# NS_ARM_Control_07_17_2017.net
KiCad netlist of a schematic drawn in EAGLE
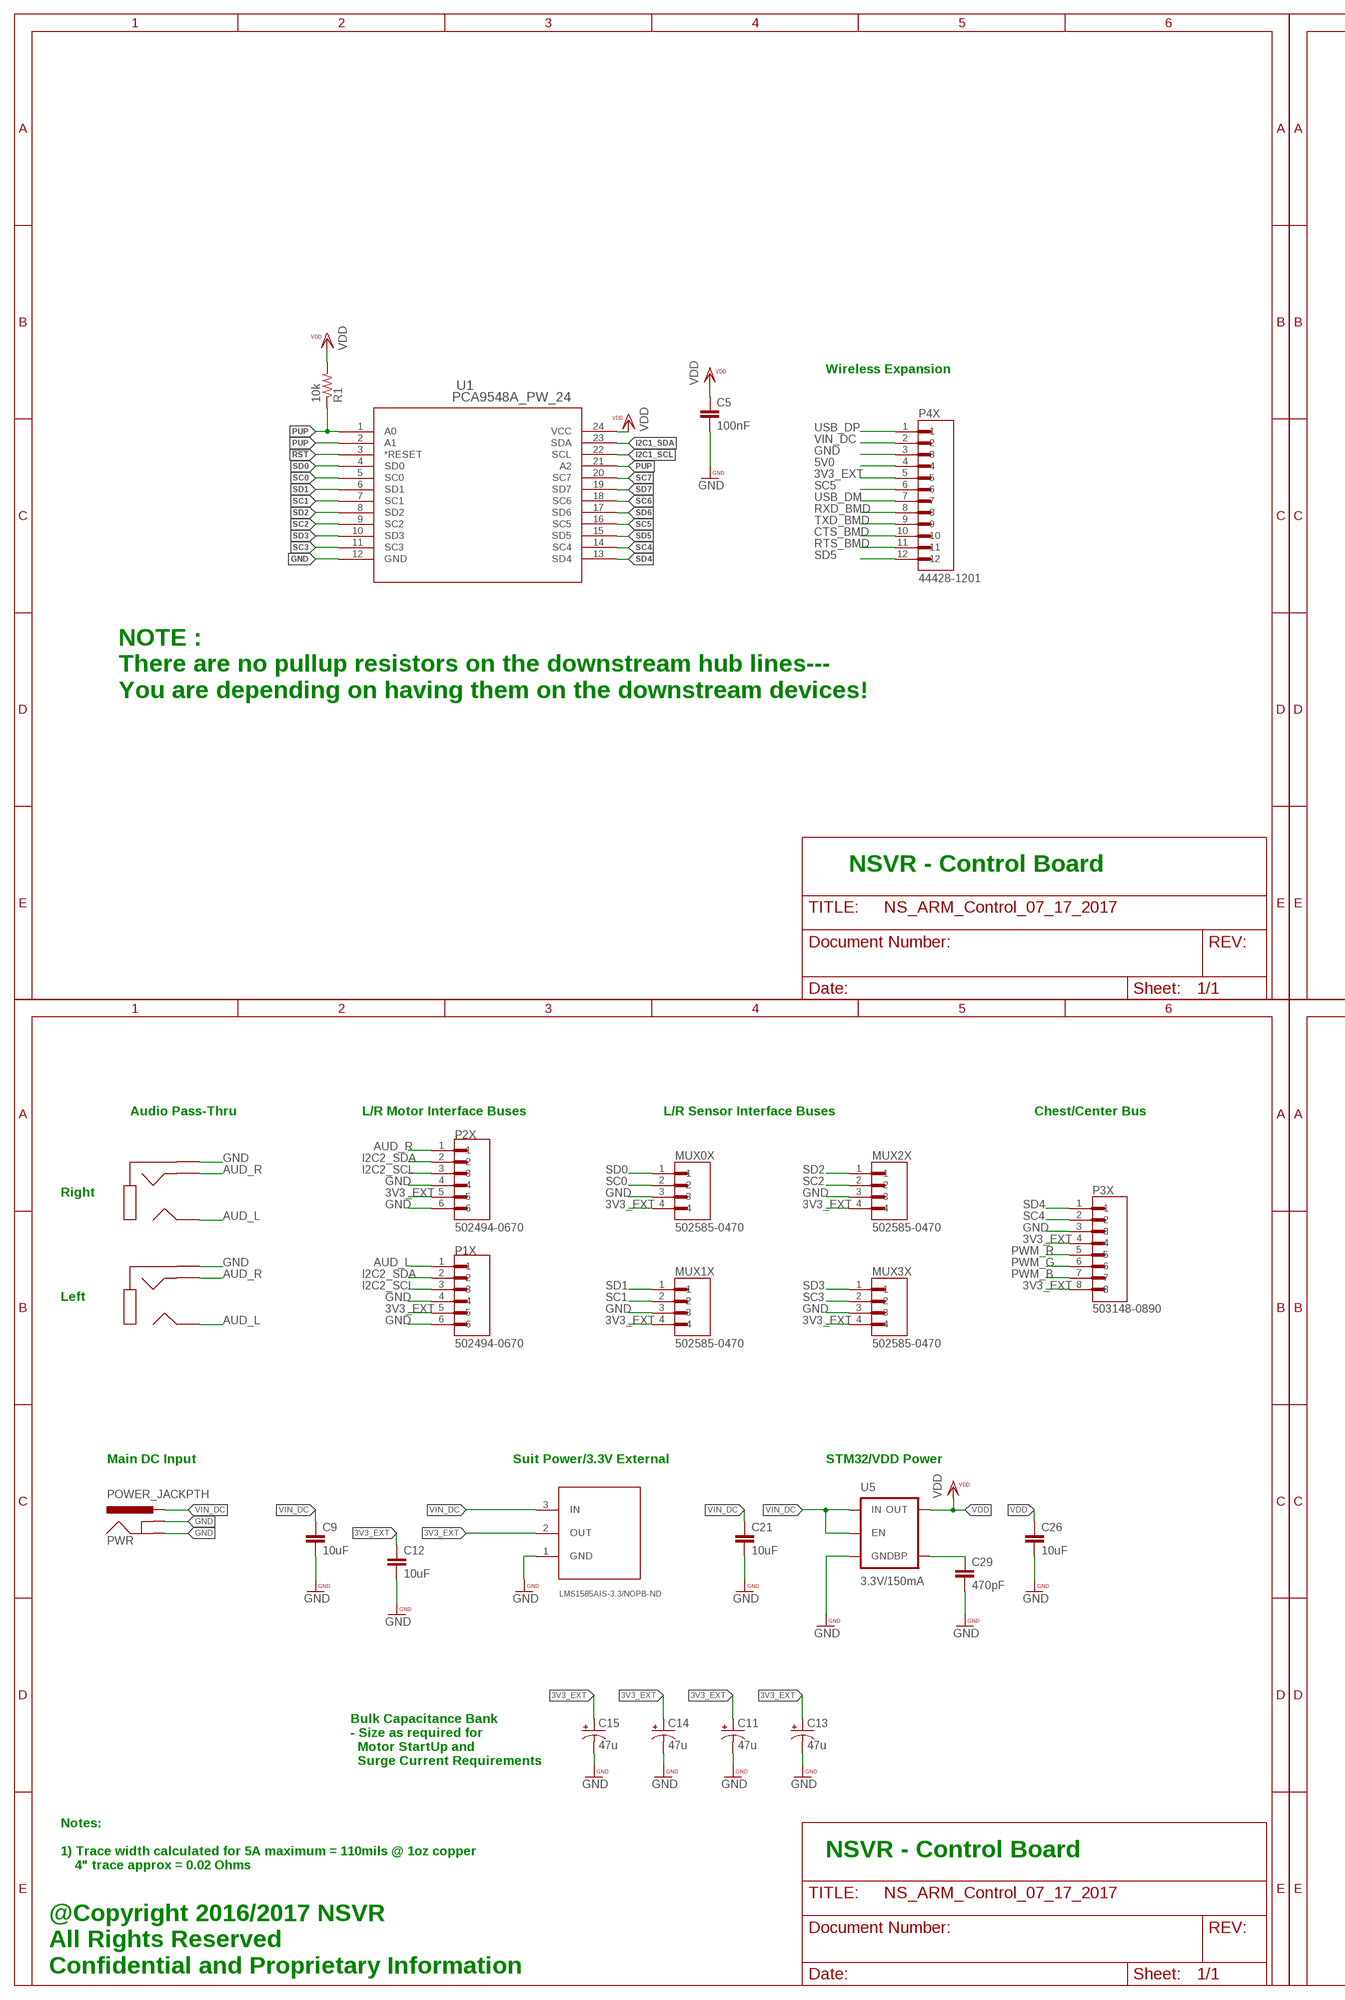
[diagram p0: schematic, sheet 1, part 1 of 2]
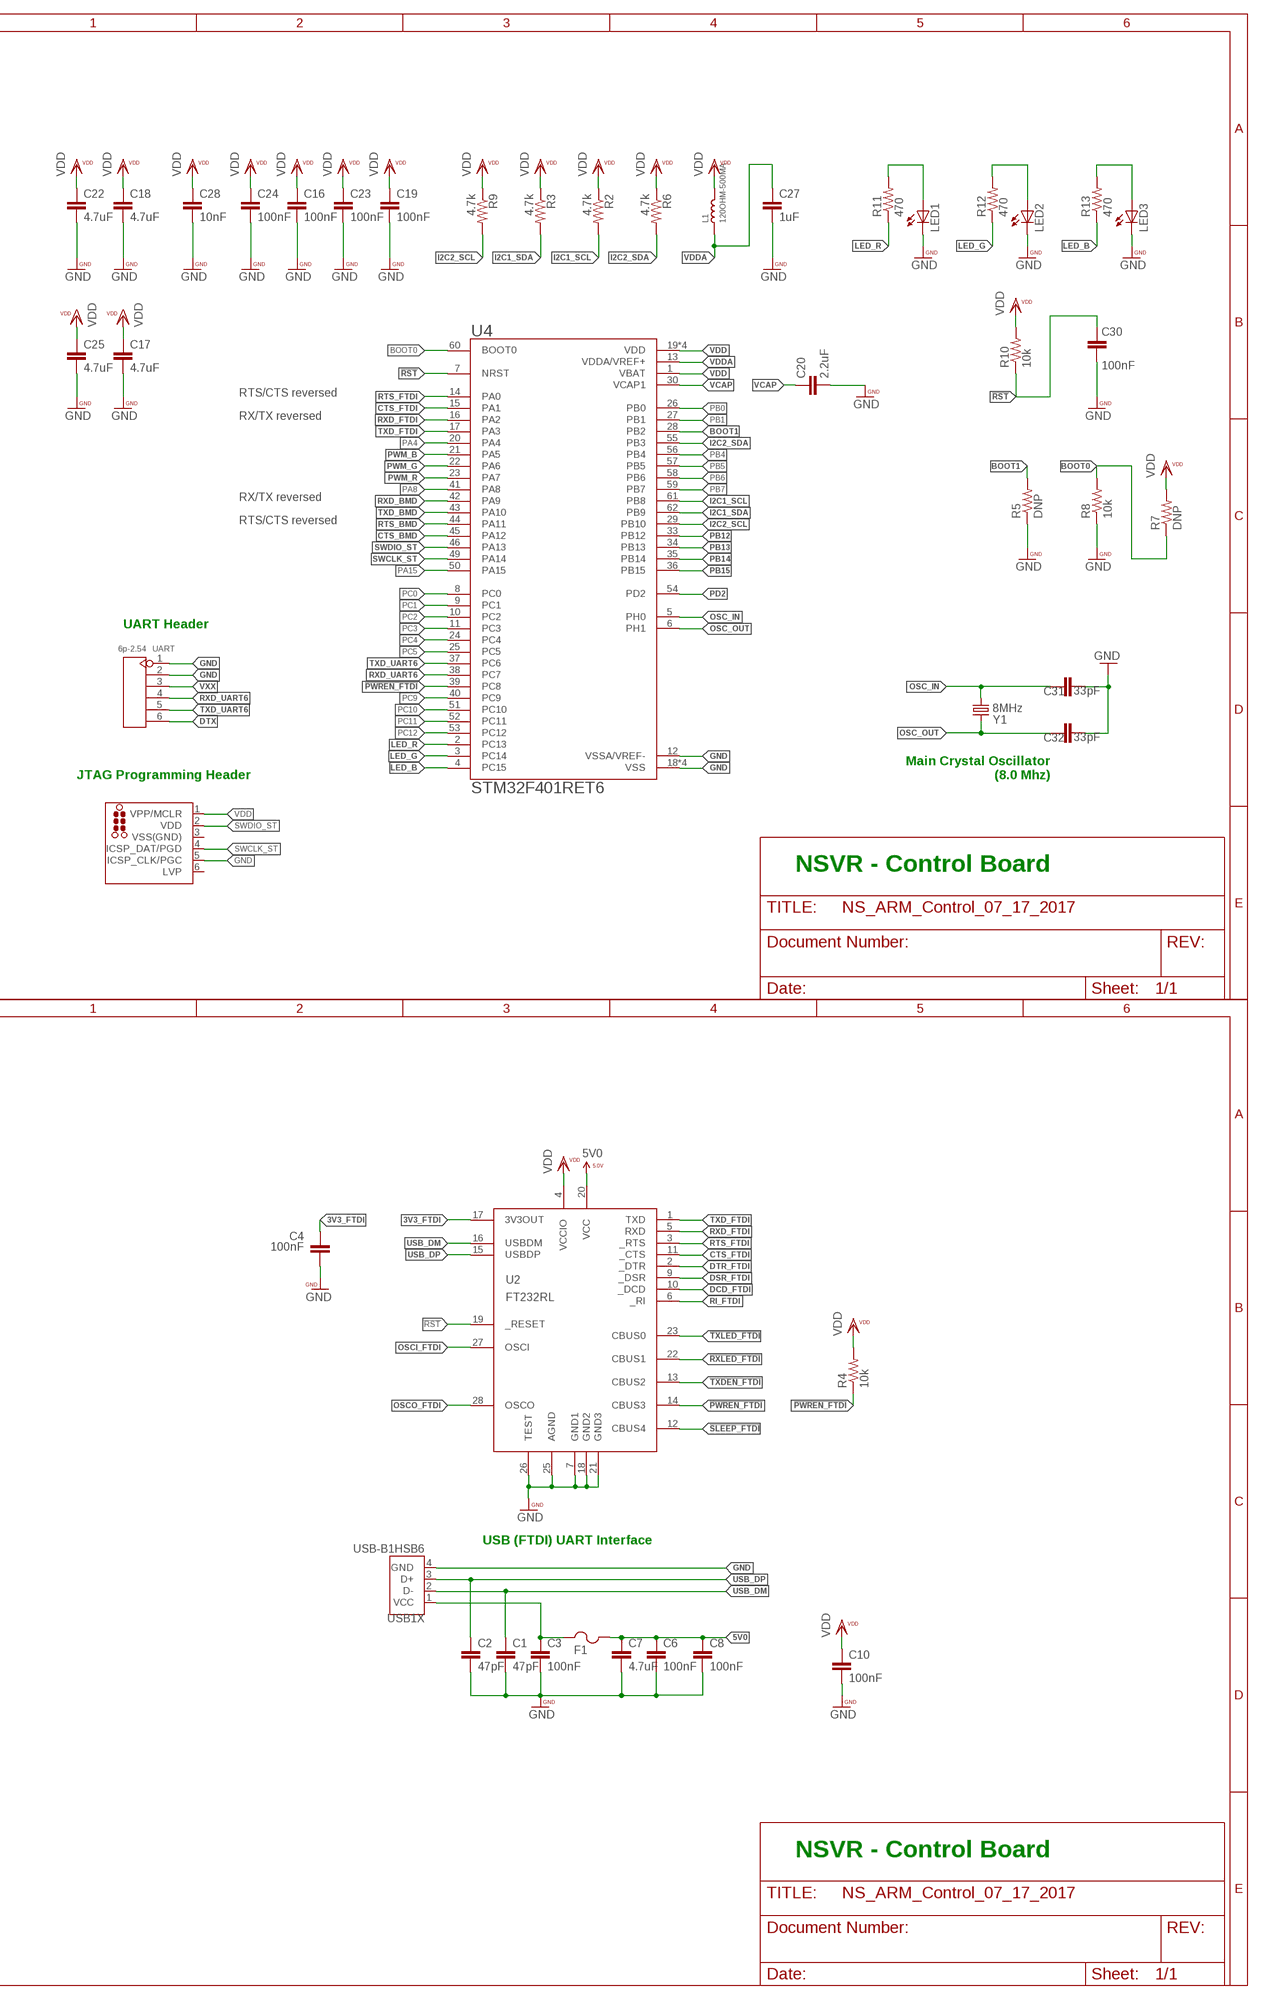
[diagram p1: schematic, sheet 1, part 2 of 2]

(export (version "E")
  (design (tool "Eeschema 10.0.6"))
  (components
    (comp (ref "C1")
      (value "47pF")
      (footprint "eagle-import:0402-CAP")
      (libsource (lib "eagle-import") (part "CAP0402-CAP"))
    )
    (comp (ref "C2")
      (value "47pF")
      (footprint "eagle-import:0402-CAP")
      (libsource (lib "eagle-import") (part "CAP0402-CAP"))
    )
    (comp (ref "C3")
      (value "100nF")
      (footprint "eagle-import:0402-CAP")
      (libsource (lib "eagle-import") (part "CAP0402-CAP"))
    )
    (comp (ref "C4")
      (value "100nF")
      (footprint "eagle-import:0402-CAP")
      (libsource (lib "eagle-import") (part "CAP0402-CAP"))
    )
    (comp (ref "C5")
      (value "100nF")
      (footprint "eagle-import:0402-CAP")
      (libsource (lib "eagle-import") (part "CAP0402-CAP"))
    )
    (comp (ref "C6")
      (value "100nF")
      (footprint "eagle-import:0402-CAP")
      (libsource (lib "eagle-import") (part "CAP0402-CAP"))
    )
    (comp (ref "C7")
      (value "4.7uF")
      (footprint "eagle-import:0402-CAP")
      (libsource (lib "eagle-import") (part "CAP0402-CAP"))
    )
    (comp (ref "C8")
      (value "100nF")
      (footprint "eagle-import:0402-CAP")
      (libsource (lib "eagle-import") (part "CAP0402-CAP"))
    )
    (comp (ref "C9")
      (value "10uF")
      (footprint "eagle-import:0603-CAP")
      (libsource (lib "eagle-import") (part "CAP0603-CAP"))
    )
    (comp (ref "C10")
      (value "100nF")
      (footprint "eagle-import:0402-CAP")
      (libsource (lib "eagle-import") (part "CAP0402-CAP"))
    )
    (comp (ref "C11")
      (value "47u")
      (footprint "eagle-import:PANASONIC_D")
      (libsource (lib "eagle-import") (part "CAP_POLD"))
    )
    (comp (ref "C12")
      (value "10uF")
      (footprint "eagle-import:0603-CAP")
      (libsource (lib "eagle-import") (part "CAP0603-CAP"))
    )
    (comp (ref "C13")
      (value "47u")
      (footprint "eagle-import:PANASONIC_D")
      (libsource (lib "eagle-import") (part "CAP_POLD"))
    )
    (comp (ref "C14")
      (value "47u")
      (footprint "eagle-import:PANASONIC_D")
      (libsource (lib "eagle-import") (part "CAP_POLD"))
    )
    (comp (ref "C15")
      (value "47u")
      (footprint "eagle-import:PANASONIC_D")
      (libsource (lib "eagle-import") (part "CAP_POLD"))
    )
    (comp (ref "C16")
      (value "100nF")
      (footprint "eagle-import:0402-CAP")
      (libsource (lib "eagle-import") (part "CAP0402-CAP"))
    )
    (comp (ref "C17")
      (value "4.7uF")
      (footprint "eagle-import:0402-CAP")
      (libsource (lib "eagle-import") (part "CAP0402-CAP"))
    )
    (comp (ref "C18")
      (value "4.7uF")
      (footprint "eagle-import:0402-CAP")
      (libsource (lib "eagle-import") (part "CAP0402-CAP"))
    )
    (comp (ref "C19")
      (value "100nF")
      (footprint "eagle-import:0402-CAP")
      (libsource (lib "eagle-import") (part "CAP0402-CAP"))
    )
    (comp (ref "C20")
      (value "2.2uF")
      (footprint "eagle-import:0402-CAP")
      (libsource (lib "eagle-import") (part "CAP0402-CAP"))
    )
    (comp (ref "C21")
      (value "10uF")
      (footprint "eagle-import:0603-CAP")
      (libsource (lib "eagle-import") (part "CAP0603-CAP"))
    )
    (comp (ref "C22")
      (value "4.7uF")
      (footprint "eagle-import:0402-CAP")
      (libsource (lib "eagle-import") (part "CAP0402-CAP"))
    )
    (comp (ref "C23")
      (value "100nF")
      (footprint "eagle-import:0402-CAP")
      (libsource (lib "eagle-import") (part "CAP0402-CAP"))
    )
    (comp (ref "C24")
      (value "100nF")
      (footprint "eagle-import:0402-CAP")
      (libsource (lib "eagle-import") (part "CAP0402-CAP"))
    )
    (comp (ref "C25")
      (value "4.7uF")
      (footprint "eagle-import:0402-CAP")
      (libsource (lib "eagle-import") (part "CAP0402-CAP"))
    )
    (comp (ref "C26")
      (value "10uF")
      (footprint "eagle-import:0603-CAP")
      (libsource (lib "eagle-import") (part "CAP0603-CAP"))
    )
    (comp (ref "C27")
      (value "1uF")
      (footprint "eagle-import:0402-CAP")
      (libsource (lib "eagle-import") (part "CAP0402-CAP"))
    )
    (comp (ref "C28")
      (value "10nF")
      (footprint "eagle-import:0402-CAP")
      (libsource (lib "eagle-import") (part "CAP0402-CAP"))
    )
    (comp (ref "C29")
      (value "470pF")
      (footprint "eagle-import:0402-CAP")
      (libsource (lib "eagle-import") (part "CAP0402-CAP"))
    )
    (comp (ref "C30")
      (value "100nF")
      (footprint "eagle-import:0402-CAP")
      (libsource (lib "eagle-import") (part "CAP0402-CAP"))
    )
    (comp (ref "C31")
      (value "33pF")
      (footprint "eagle-import:0402-CAP")
      (libsource (lib "eagle-import") (part "CAP0402-CAP"))
    )
    (comp (ref "C32")
      (value "33pF")
      (footprint "eagle-import:0402-CAP")
      (libsource (lib "eagle-import") (part "CAP0402-CAP"))
    )
    (comp (ref "F1")
      (value "1206L050YR")
      (footprint "eagle-import:1206LSERIES")
      (fields (field (name "COPYRIGHT") "Copyright C 2015 Accelerated Designs. All rights reserved"))
      (libsource (lib "eagle-import") (part "1206L050YR"))
    )
    (comp (ref "J_ST")
      (value "TC2030-MCP-NL")
      (footprint "eagle-import:TC2030-MCP-NL")
      (libsource (lib "eagle-import") (part "TC2030-MCP-NL"))
    )
    (comp (ref "L1")
      (value "120OHM-500MA")
      (footprint "eagle-import:L0603")
      (fields (field (name "MPN") "BLM18AG121SN1D"))
      (libsource (lib "eagle-import") (part "SMD-FERRITE-CHIP-120-OHM-500MA(0603)"))
    )
    (comp (ref "LED1")
      (value "LEDCHIP-LED0603")
      (footprint "eagle-import:CHIP-LED0603")
      (libsource (lib "eagle-import") (part "LEDCHIP-LED0603"))
    )
    (comp (ref "LED2")
      (value "LEDCHIP-LED0603")
      (footprint "eagle-import:CHIP-LED0603")
      (libsource (lib "eagle-import") (part "LEDCHIP-LED0603"))
    )
    (comp (ref "LED3")
      (value "LEDCHIP-LED0603")
      (footprint "eagle-import:CHIP-LED0603")
      (libsource (lib "eagle-import") (part "LEDCHIP-LED0603"))
    )
    (comp (ref "MUX0X")
      (value "502585-0470")
      (footprint "eagle-import:MOLEX_502585-0470")
      (fields (field (name "MF") "Molex"))
      (libsource (lib "eagle-import") (part "502585-0470"))
    )
    (comp (ref "MUX1X")
      (value "502585-0470")
      (footprint "eagle-import:MOLEX_502585-0470")
      (fields (field (name "MF") "Molex"))
      (libsource (lib "eagle-import") (part "502585-0470"))
    )
    (comp (ref "MUX2X")
      (value "502585-0470")
      (footprint "eagle-import:MOLEX_502585-0470")
      (fields (field (name "MF") "Molex"))
      (libsource (lib "eagle-import") (part "502585-0470"))
    )
    (comp (ref "MUX3X")
      (value "502585-0470")
      (footprint "eagle-import:MOLEX_502585-0470")
      (fields (field (name "MF") "Molex"))
      (libsource (lib "eagle-import") (part "502585-0470"))
    )
    (comp (ref "P1X")
      (value "502494-0670")
      (footprint "eagle-import:MOLEX_502494-0670")
      (fields (field (name "MF") "Molex"))
      (libsource (lib "eagle-import") (part "502494-0670"))
    )
    (comp (ref "P2X")
      (value "502494-0670")
      (footprint "eagle-import:MOLEX_502494-0670")
      (fields (field (name "MF") "Molex"))
      (libsource (lib "eagle-import") (part "502494-0670"))
    )
    (comp (ref "P3X")
      (value "503148-0890")
      (footprint "eagle-import:MOLEX_503148-0890")
      (fields (field (name "MF") "Molex"))
      (libsource (lib "eagle-import") (part "503148-0890"))
    )
    (comp (ref "P4X")
      (value "44428-1201")
      (footprint "eagle-import:MOLEX_44428-1201")
      (fields (field (name "MF") "Molex"))
      (libsource (lib "eagle-import") (part "44428-1201"))
    )
    (comp (ref "PJ1")
      (value "SJ1-3513N")
      (footprint "eagle-import:SJ1-351XN")
      (libsource (lib "eagle-import") (part "SJ1-3513N"))
    )
    (comp (ref "PJ2")
      (value "SJ1-3513N")
      (footprint "eagle-import:SJ1-351XN")
      (libsource (lib "eagle-import") (part "SJ1-3513N"))
    )
    (comp (ref "PWR")
      (value "POWER_JACKPTH")
      (footprint "eagle-import:POWER_JACK_PTH")
      (libsource (lib "eagle-import") (part "POWER_JACKPTH"))
    )
    (comp (ref "R1")
      (value "10k")
      (footprint "eagle-import:EIA-0402")
      (libsource (lib "eagle-import") (part "RESISTOR0402-TYP"))
    )
    (comp (ref "R2")
      (value "4.7k")
      (footprint "eagle-import:EIA-0402")
      (libsource (lib "eagle-import") (part "RESISTOR0402-TYP"))
    )
    (comp (ref "R3")
      (value "4.7k")
      (footprint "eagle-import:EIA-0402")
      (libsource (lib "eagle-import") (part "RESISTOR0402-TYP"))
    )
    (comp (ref "R4")
      (value "10k")
      (footprint "eagle-import:EIA-0402")
      (libsource (lib "eagle-import") (part "RESISTOR0402-TYP"))
    )
    (comp (ref "R5")
      (value "DNP")
      (footprint "eagle-import:EIA-0402")
      (libsource (lib "eagle-import") (part "RESISTOR0402-TYP"))
    )
    (comp (ref "R6")
      (value "4.7k")
      (footprint "eagle-import:EIA-0402")
      (libsource (lib "eagle-import") (part "RESISTOR0402-TYP"))
    )
    (comp (ref "R7")
      (value "DNP")
      (footprint "eagle-import:EIA-0402")
      (libsource (lib "eagle-import") (part "RESISTOR0402-TYP"))
    )
    (comp (ref "R8")
      (value "10k")
      (footprint "eagle-import:EIA-0402")
      (libsource (lib "eagle-import") (part "RESISTOR0402-TYP"))
    )
    (comp (ref "R9")
      (value "4.7k")
      (footprint "eagle-import:EIA-0402")
      (libsource (lib "eagle-import") (part "RESISTOR0402-TYP"))
    )
    (comp (ref "R10")
      (value "10k")
      (footprint "eagle-import:EIA-0402")
      (libsource (lib "eagle-import") (part "RESISTOR0402-TYP"))
    )
    (comp (ref "R11")
      (value "470")
      (footprint "eagle-import:EIA-0402")
      (libsource (lib "eagle-import") (part "RESISTOR0402-TYP"))
    )
    (comp (ref "R12")
      (value "470")
      (footprint "eagle-import:EIA-0402")
      (libsource (lib "eagle-import") (part "RESISTOR0402-TYP"))
    )
    (comp (ref "R13")
      (value "470")
      (footprint "eagle-import:EIA-0402")
      (libsource (lib "eagle-import") (part "RESISTOR0402-TYP"))
    )
    (comp (ref "U1")
      (value "PCA9548A_PW_24")
      (footprint "eagle-import:PW24")
      (fields
        (field (name "GENERIC_PART_NUMBER") "PCA9548A")
        (field (name "MANUFACTURER") "Texas Instruments")
        (field (name "MANUFACTURER_PART_NUMBER") "pca9548a_pw_24")
      )
      (libsource (lib "eagle-import") (part "PCA9548A_PW_24"))
    )
    (comp (ref "U2")
      (value "FT232RL")
      (footprint "eagle-import:SSOP28DB")
      (libsource (lib "eagle-import") (part "FT232RL"))
    )
    (comp (ref "U3")
      (value "LMS1585AIS-3.3/NOPB-ND")
      (footprint "eagle-import:TO254P1524X483-4N")
      (libsource (lib "eagle-import") (part "LMS1585AIS-3.3/NOPB-ND"))
    )
    (comp (ref "U4")
      (value "STM32F401RET6")
      (footprint "eagle-import:QFP50P1200X1200X160-64N")
      (fields (field (name "MF") "STMicroelectronics"))
      (libsource (lib "eagle-import") (part "STM32F401RET6"))
    )
    (comp (ref "U5")
      (value "3.3V/150mA")
      (footprint "eagle-import:SOT23-5")
      (libsource (lib "eagle-import") (part "V_REG_MIC52053.3V"))
    )
    (comp (ref "UART")
      (value "6p-2.54")
      (footprint "eagle-import:H6-2.54")
      (fields (field (name "MPN") "F185-1106A1BSYC1"))
      (libsource (lib "eagle-import") (part "DIP-BLACK-FEMALE-HEADER-VERT(6P-2.54)"))
    )
    (comp (ref "USB1X")
      (value "USB-B1HSB6")
      (footprint "eagle-import:OST_USB-B1HSB6")
      (fields (field (name "MF") "On Shore Technology"))
      (libsource (lib "eagle-import") (part "USB-B1HSB6"))
    )
    (comp (ref "Y1")
      (value "8MHz")
      (footprint "eagle-import:CRYSTAL-SMD-5X3")
      (libsource (lib "eagle-import") (part "CRYSTAL5X3"))
    )
  )
  (nets
    (net (code "1") (name "/AUD_L") (class "Default")
      (node (ref "P1X") (pin "1") (pinfunction "1_1") (pintype "passive"))
      (node (ref "PJ1") (pin "2") (pinfunction "2_2") (pintype "bidirectional"))
      (node (ref "PJ2") (pin "2") (pinfunction "2_2") (pintype "bidirectional"))
    )
    (net (code "2") (name "/AUD_R") (class "Default")
      (node (ref "P2X") (pin "1") (pinfunction "1_1") (pintype "passive"))
      (node (ref "PJ1") (pin "3") (pinfunction "3_3") (pintype "bidirectional"))
      (node (ref "PJ2") (pin "3") (pinfunction "3_3") (pintype "bidirectional"))
    )
    (net (code "3") (name "/VSS(GND)") (class "Default")
      (node (ref "J_ST") (pin "3") (pinfunction "VSS(GND)_3") (pintype "power_in"))
    )
    (net (code "4") (name "/~{PWREN_FTDI}") (class "Default")
      (node (ref "R4") (pin "1") (pinfunction "1_1") (pintype "passive"))
      (node (ref "U2") (pin "14") (pinfunction "CBUS3_14") (pintype "bidirectional"))
      (node (ref "U4") (pin "39") (pinfunction "PC8_39") (pintype "bidirectional"))
    )
    (net (code "5") (name "/~{RST}") (class "Default")
      (node (ref "C30") (pin "1") (pinfunction "1_1") (pintype "passive"))
      (node (ref "R10") (pin "1") (pinfunction "1_1") (pintype "passive"))
      (node (ref "U1") (pin "3") (pinfunction "*RESET_3") (pintype "input"))
      (node (ref "U2") (pin "19") (pinfunction "_RESET_19") (pintype "input"))
      (node (ref "U4") (pin "7") (pinfunction "NRST_7") (pintype "bidirectional"))
    )
    (net (code "6") (name "/~{RXLED_FTDI}") (class "Default")
      (node (ref "U2") (pin "22") (pinfunction "CBUS1_22") (pintype "bidirectional"))
    )
    (net (code "7") (name "/~{SLEEP_FTDI}") (class "Default")
      (node (ref "U2") (pin "12") (pinfunction "CBUS4_12") (pintype "bidirectional"))
    )
    (net (code "8") (name "/~{TXDEN_FTDI}") (class "Default")
      (node (ref "U2") (pin "13") (pinfunction "CBUS2_13") (pintype "bidirectional"))
    )
    (net (code "9") (name "/~{TXLED_FTDI}") (class "Default")
      (node (ref "U2") (pin "23") (pinfunction "CBUS0_23") (pintype "bidirectional"))
    )
    (net (code "10") (name "3V3_EXT") (class "Default")
      (node (ref "C11") (pin "+") (pinfunction "+_+") (pintype "passive"))
      (node (ref "C12") (pin "1") (pinfunction "1_1") (pintype "passive"))
      (node (ref "C13") (pin "+") (pinfunction "+_+") (pintype "passive"))
      (node (ref "C14") (pin "+") (pinfunction "+_+") (pintype "passive"))
      (node (ref "C15") (pin "+") (pinfunction "+_+") (pintype "passive"))
      (node (ref "MUX0X") (pin "4") (pinfunction "4_4") (pintype "passive"))
      (node (ref "MUX1X") (pin "4") (pinfunction "4_4") (pintype "passive"))
      (node (ref "MUX2X") (pin "4") (pinfunction "4_4") (pintype "passive"))
      (node (ref "MUX3X") (pin "4") (pinfunction "4_4") (pintype "passive"))
      (node (ref "P1X") (pin "5") (pinfunction "5_5") (pintype "passive"))
      (node (ref "P2X") (pin "5") (pinfunction "5_5") (pintype "passive"))
      (node (ref "P3X") (pin "4") (pinfunction "4_4") (pintype "passive"))
      (node (ref "P3X") (pin "8") (pinfunction "8_8") (pintype "passive"))
      (node (ref "P4X") (pin "5") (pinfunction "5_5") (pintype "passive"))
      (node (ref "U3") (pin "2") (pinfunction "OUT_2") (pintype "bidirectional"))
    )
    (net (code "11") (name "3V3_FTDI") (class "Default")
      (node (ref "C4") (pin "1") (pinfunction "1_1") (pintype "passive"))
      (node (ref "U2") (pin "17") (pinfunction "3V3OUT_17") (pintype "output"))
    )
    (net (code "12") (name "5V0") (class "Default")
      (node (ref "C6") (pin "1") (pinfunction "1_1") (pintype "passive"))
      (node (ref "C7") (pin "1") (pinfunction "1_1") (pintype "passive"))
      (node (ref "C8") (pin "1") (pinfunction "1_1") (pintype "passive"))
      (node (ref "F1") (pin "2") (pinfunction "2_2") (pintype "passive"))
      (node (ref "P4X") (pin "4") (pinfunction "4_4") (pintype "passive"))
      (node (ref "U2") (pin "20") (pinfunction "VCC_20") (pintype "power_in"))
    )
    (net (code "13") (name "BOOT0") (class "Default")
      (node (ref "R7") (pin "1") (pinfunction "1_1") (pintype "passive"))
      (node (ref "R8") (pin "2") (pinfunction "2_2") (pintype "passive"))
      (node (ref "U4") (pin "60") (pinfunction "BOOT0_60") (pintype "input"))
    )
    (net (code "14") (name "BOOT1") (class "Default")
      (node (ref "R5") (pin "2") (pinfunction "2_2") (pintype "passive"))
      (node (ref "U4") (pin "28") (pinfunction "PB2_28") (pintype "bidirectional"))
    )
    (net (code "15") (name "CTS_BMD") (class "Default")
      (node (ref "P4X") (pin "10") (pinfunction "10_10") (pintype "passive"))
      (node (ref "U4") (pin "45") (pinfunction "PA12_45") (pintype "bidirectional"))
    )
    (net (code "16") (name "CTS_FTDI") (class "Default")
      (node (ref "U2") (pin "11") (pinfunction "_CTS_11") (pintype "input"))
      (node (ref "U4") (pin "15") (pinfunction "PA1_15") (pintype "bidirectional"))
    )
    (net (code "17") (name "DCD_FTDI") (class "Default")
      (node (ref "U2") (pin "10") (pinfunction "_DCD_10") (pintype "input"))
    )
    (net (code "18") (name "DSR_FTDI") (class "Default")
      (node (ref "U2") (pin "9") (pinfunction "_DSR_9") (pintype "input"))
    )
    (net (code "19") (name "DTR_FTDI") (class "Default")
      (node (ref "U2") (pin "2") (pinfunction "_DTR_2") (pintype "output"))
    )
    (net (code "20") (name "DTX") (class "Default")
      (node (ref "UART") (pin "6") (pinfunction "6_6") (pintype "bidirectional"))
    )
    (net (code "21") (name "GND") (class "Default")
      (node (ref "C1") (pin "2") (pinfunction "2_2") (pintype "passive"))
      (node (ref "C10") (pin "2") (pinfunction "2_2") (pintype "passive"))
      (node (ref "C11") (pin "-") (pinfunction "-_-") (pintype "passive"))
      (node (ref "C12") (pin "2") (pinfunction "2_2") (pintype "passive"))
      (node (ref "C13") (pin "-") (pinfunction "-_-") (pintype "passive"))
      (node (ref "C14") (pin "-") (pinfunction "-_-") (pintype "passive"))
      (node (ref "C15") (pin "-") (pinfunction "-_-") (pintype "passive"))
      (node (ref "C16") (pin "2") (pinfunction "2_2") (pintype "passive"))
      (node (ref "C17") (pin "2") (pinfunction "2_2") (pintype "passive"))
      (node (ref "C18") (pin "2") (pinfunction "2_2") (pintype "passive"))
      (node (ref "C19") (pin "2") (pinfunction "2_2") (pintype "passive"))
      (node (ref "C2") (pin "2") (pinfunction "2_2") (pintype "passive"))
      (node (ref "C20") (pin "2") (pinfunction "2_2") (pintype "passive"))
      (node (ref "C21") (pin "2") (pinfunction "2_2") (pintype "passive"))
      (node (ref "C22") (pin "2") (pinfunction "2_2") (pintype "passive"))
      (node (ref "C23") (pin "2") (pinfunction "2_2") (pintype "passive"))
      (node (ref "C24") (pin "2") (pinfunction "2_2") (pintype "passive"))
      (node (ref "C25") (pin "2") (pinfunction "2_2") (pintype "passive"))
      (node (ref "C26") (pin "2") (pinfunction "2_2") (pintype "passive"))
      (node (ref "C27") (pin "2") (pinfunction "2_2") (pintype "passive"))
      (node (ref "C28") (pin "2") (pinfunction "2_2") (pintype "passive"))
      (node (ref "C29") (pin "2") (pinfunction "2_2") (pintype "passive"))
      (node (ref "C3") (pin "2") (pinfunction "2_2") (pintype "passive"))
      (node (ref "C30") (pin "2") (pinfunction "2_2") (pintype "passive"))
      (node (ref "C31") (pin "1") (pinfunction "1_1") (pintype "passive"))
      (node (ref "C32") (pin "1") (pinfunction "1_1") (pintype "passive"))
      (node (ref "C4") (pin "2") (pinfunction "2_2") (pintype "passive"))
      (node (ref "C5") (pin "2") (pinfunction "2_2") (pintype "passive"))
      (node (ref "C6") (pin "2") (pinfunction "2_2") (pintype "passive"))
      (node (ref "C7") (pin "2") (pinfunction "2_2") (pintype "passive"))
      (node (ref "C8") (pin "2") (pinfunction "2_2") (pintype "passive"))
      (node (ref "C9") (pin "2") (pinfunction "2_2") (pintype "passive"))
      (node (ref "J_ST") (pin "5") (pinfunction "ICSP_CLK/PGC_5") (pintype "output"))
      (node (ref "LED1") (pin "C") (pinfunction "C_C") (pintype "passive"))
      (node (ref "LED2") (pin "C") (pinfunction "C_C") (pintype "passive"))
      (node (ref "LED3") (pin "C") (pinfunction "C_C") (pintype "passive"))
      (node (ref "MUX0X") (pin "3") (pinfunction "3_3") (pintype "passive"))
      (node (ref "MUX1X") (pin "3") (pinfunction "3_3") (pintype "passive"))
      (node (ref "MUX2X") (pin "3") (pinfunction "3_3") (pintype "passive"))
      (node (ref "MUX3X") (pin "3") (pinfunction "3_3") (pintype "passive"))
      (node (ref "P1X") (pin "4") (pinfunction "4_4") (pintype "passive"))
      (node (ref "P1X") (pin "6") (pinfunction "6_6") (pintype "passive"))
      (node (ref "P2X") (pin "4") (pinfunction "4_4") (pintype "passive"))
      (node (ref "P2X") (pin "6") (pinfunction "6_6") (pintype "passive"))
      (node (ref "P3X") (pin "3") (pinfunction "3_3") (pintype "passive"))
      (node (ref "P4X") (pin "3") (pinfunction "3_3") (pintype "passive"))
      (node (ref "PJ1") (pin "1") (pinfunction "1_1") (pintype "bidirectional"))
      (node (ref "PJ2") (pin "1") (pinfunction "1_1") (pintype "bidirectional"))
      (node (ref "PWR") (pin "GND") (pinfunction "GND_GND") (pintype "bidirectional"))
      (node (ref "PWR") (pin "GNDBREAK") (pinfunction "GNDBREAK_GNDBREAK") (pintype "bidirectional"))
      (node (ref "R5") (pin "1") (pinfunction "1_1") (pintype "passive"))
      (node (ref "R8") (pin "1") (pinfunction "1_1") (pintype "passive"))
      (node (ref "U1") (pin "12") (pinfunction "GND_12") (pintype "power_in"))
      (node (ref "U2") (pin "18") (pinfunction "GND2_18") (pintype "power_in"))
      (node (ref "U2") (pin "21") (pinfunction "GND3_21") (pintype "power_in"))
      (node (ref "U2") (pin "25") (pinfunction "AGND_25") (pintype "power_in"))
      (node (ref "U2") (pin "26") (pinfunction "TEST_26") (pintype "input"))
      (node (ref "U2") (pin "7") (pinfunction "GND1_7") (pintype "power_in"))
      (node (ref "U3") (pin "1") (pinfunction "GND_1") (pintype "bidirectional"))
      (node (ref "U4") (pin "12") (pinfunction "VSSA/VREF-_12") (pintype "power_in"))
      (node (ref "U4") (pin "18") (pinfunction "VSS_18") (pintype "power_in"))
      (node (ref "U4") (pin "31") (pinfunction "VSS_31") (pintype "power_in"))
      (node (ref "U4") (pin "47") (pinfunction "VSS_47") (pintype "power_in"))
      (node (ref "U4") (pin "63") (pinfunction "VSS_63") (pintype "power_in"))
      (node (ref "U5") (pin "2") (pinfunction "GND_2") (pintype "input"))
      (node (ref "UART") (pin "1") (pinfunction "1_1") (pintype "bidirectional"))
      (node (ref "UART") (pin "2") (pinfunction "2_2") (pintype "bidirectional"))
      (node (ref "USB1X") (pin "4") (pinfunction "GND_4") (pintype "power_in"))
    )
    (net (code "22") (name "I2C1_SCL") (class "Default")
      (node (ref "R2") (pin "2") (pinfunction "2_2") (pintype "passive"))
      (node (ref "U1") (pin "22") (pinfunction "SCL_22") (pintype "passive"))
      (node (ref "U4") (pin "61") (pinfunction "PB8_61") (pintype "bidirectional"))
    )
    (net (code "23") (name "I2C1_SDA") (class "Default")
      (node (ref "R3") (pin "2") (pinfunction "2_2") (pintype "passive"))
      (node (ref "U1") (pin "23") (pinfunction "SDA_23") (pintype "passive"))
      (node (ref "U4") (pin "62") (pinfunction "PB9_62") (pintype "bidirectional"))
    )
    (net (code "24") (name "I2C2_SCL") (class "Default")
      (node (ref "P1X") (pin "3") (pinfunction "3_3") (pintype "passive"))
      (node (ref "P2X") (pin "3") (pinfunction "3_3") (pintype "passive"))
      (node (ref "R9") (pin "2") (pinfunction "2_2") (pintype "passive"))
      (node (ref "U4") (pin "29") (pinfunction "PB10_29") (pintype "bidirectional"))
    )
    (net (code "25") (name "I2C2_SDA") (class "Default")
      (node (ref "P1X") (pin "2") (pinfunction "2_2") (pintype "passive"))
      (node (ref "P2X") (pin "2") (pinfunction "2_2") (pintype "passive"))
      (node (ref "R6") (pin "2") (pinfunction "2_2") (pintype "passive"))
      (node (ref "U4") (pin "55") (pinfunction "PB3_55") (pintype "bidirectional"))
    )
    (net (code "26") (name "LED_B") (class "Default")
      (node (ref "R13") (pin "1") (pinfunction "1_1") (pintype "passive"))
      (node (ref "U4") (pin "4") (pinfunction "PC15_4") (pintype "bidirectional"))
    )
    (net (code "27") (name "LED_G") (class "Default")
      (node (ref "R12") (pin "1") (pinfunction "1_1") (pintype "passive"))
      (node (ref "U4") (pin "3") (pinfunction "PC14_3") (pintype "bidirectional"))
    )
    (net (code "28") (name "LED_R") (class "Default")
      (node (ref "R11") (pin "1") (pinfunction "1_1") (pintype "passive"))
      (node (ref "U4") (pin "2") (pinfunction "PC13_2") (pintype "bidirectional"))
    )
    (net (code "29") (name "Net-(LED1-PadA)") (class "Default")
      (node (ref "LED1") (pin "A") (pinfunction "A_A") (pintype "passive"))
      (node (ref "R11") (pin "2") (pinfunction "2_2") (pintype "passive"))
    )
    (net (code "30") (name "Net-(LED2-PadA)") (class "Default")
      (node (ref "LED2") (pin "A") (pinfunction "A_A") (pintype "passive"))
      (node (ref "R12") (pin "2") (pinfunction "2_2") (pintype "passive"))
    )
    (net (code "31") (name "Net-(LED3-PadA)") (class "Default")
      (node (ref "LED3") (pin "A") (pinfunction "A_A") (pintype "passive"))
      (node (ref "R13") (pin "2") (pinfunction "2_2") (pintype "passive"))
    )
    (net (code "32") (name "Net-(U5-BP)") (class "Default")
      (node (ref "C29") (pin "1") (pinfunction "1_1") (pintype "passive"))
      (node (ref "U5") (pin "4") (pinfunction "BP_4") (pintype "input"))
    )
    (net (code "33") (name "Net-(USB1X-VCC)") (class "Default")
      (node (ref "C3") (pin "1") (pinfunction "1_1") (pintype "passive"))
      (node (ref "F1") (pin "1") (pinfunction "1_1") (pintype "passive"))
      (node (ref "USB1X") (pin "1") (pinfunction "VCC_1") (pintype "power_in"))
    )
    (net (code "34") (name "OSCI_FTDI") (class "Default")
      (node (ref "U2") (pin "27") (pinfunction "OSCI_27") (pintype "input"))
    )
    (net (code "35") (name "OSCO_FTDI") (class "Default")
      (node (ref "U2") (pin "28") (pinfunction "OSCO_28") (pintype "output"))
    )
    (net (code "36") (name "OSC_IN") (class "Default")
      (node (ref "C31") (pin "2") (pinfunction "2_2") (pintype "passive"))
      (node (ref "U4") (pin "5") (pinfunction "PH0_5") (pintype "bidirectional"))
      (node (ref "Y1") (pin "1") (pinfunction "1_1") (pintype "passive"))
    )
    (net (code "37") (name "OSC_OUT") (class "Default")
      (node (ref "C32") (pin "2") (pinfunction "2_2") (pintype "passive"))
      (node (ref "U4") (pin "6") (pinfunction "PH1_6") (pintype "bidirectional"))
      (node (ref "Y1") (pin "3") (pinfunction "2_3") (pintype "passive"))
    )
    (net (code "38") (name "PA4") (class "Default")
      (node (ref "U4") (pin "20") (pinfunction "PA4_20") (pintype "bidirectional"))
    )
    (net (code "39") (name "PA8") (class "Default")
      (node (ref "U4") (pin "41") (pinfunction "PA8_41") (pintype "bidirectional"))
    )
    (net (code "40") (name "PA15") (class "Default")
      (node (ref "U4") (pin "50") (pinfunction "PA15_50") (pintype "bidirectional"))
    )
    (net (code "41") (name "PB0") (class "Default")
      (node (ref "U4") (pin "26") (pinfunction "PB0_26") (pintype "bidirectional"))
    )
    (net (code "42") (name "PB1") (class "Default")
      (node (ref "U4") (pin "27") (pinfunction "PB1_27") (pintype "bidirectional"))
    )
    (net (code "43") (name "PB4") (class "Default")
      (node (ref "U4") (pin "56") (pinfunction "PB4_56") (pintype "bidirectional"))
    )
    (net (code "44") (name "PB5") (class "Default")
      (node (ref "U4") (pin "57") (pinfunction "PB5_57") (pintype "bidirectional"))
    )
    (net (code "45") (name "PB6") (class "Default")
      (node (ref "U4") (pin "58") (pinfunction "PB6_58") (pintype "bidirectional"))
    )
    (net (code "46") (name "PB7") (class "Default")
      (node (ref "U4") (pin "59") (pinfunction "PB7_59") (pintype "bidirectional"))
    )
    (net (code "47") (name "PB12") (class "Default")
      (node (ref "U4") (pin "33") (pinfunction "PB12_33") (pintype "bidirectional"))
    )
    (net (code "48") (name "PB13") (class "Default")
      (node (ref "U4") (pin "34") (pinfunction "PB13_34") (pintype "bidirectional"))
    )
    (net (code "49") (name "PB14") (class "Default")
      (node (ref "U4") (pin "35") (pinfunction "PB14_35") (pintype "bidirectional"))
    )
    (net (code "50") (name "PB15") (class "Default")
      (node (ref "U4") (pin "36") (pinfunction "PB15_36") (pintype "bidirectional"))
    )
    (net (code "51") (name "PC0") (class "Default")
      (node (ref "U4") (pin "8") (pinfunction "PC0_8") (pintype "bidirectional"))
    )
    (net (code "52") (name "PC1") (class "Default")
      (node (ref "U4") (pin "9") (pinfunction "PC1_9") (pintype "bidirectional"))
    )
    (net (code "53") (name "PC2") (class "Default")
      (node (ref "U4") (pin "10") (pinfunction "PC2_10") (pintype "bidirectional"))
    )
    (net (code "54") (name "PC3") (class "Default")
      (node (ref "U4") (pin "11") (pinfunction "PC3_11") (pintype "bidirectional"))
    )
    (net (code "55") (name "PC4") (class "Default")
      (node (ref "U4") (pin "24") (pinfunction "PC4_24") (pintype "bidirectional"))
    )
    (net (code "56") (name "PC5") (class "Default")
      (node (ref "U4") (pin "25") (pinfunction "PC5_25") (pintype "bidirectional"))
    )
    (net (code "57") (name "PC9") (class "Default")
      (node (ref "U4") (pin "40") (pinfunction "PC9_40") (pintype "bidirectional"))
    )
    (net (code "58") (name "PC10") (class "Default")
      (node (ref "U4") (pin "51") (pinfunction "PC10_51") (pintype "bidirectional"))
    )
    (net (code "59") (name "PC11") (class "Default")
      (node (ref "U4") (pin "52") (pinfunction "PC11_52") (pintype "bidirectional"))
    )
    (net (code "60") (name "PC12") (class "Default")
      (node (ref "U4") (pin "53") (pinfunction "PC12_53") (pintype "bidirectional"))
    )
    (net (code "61") (name "PD2") (class "Default")
      (node (ref "U4") (pin "54") (pinfunction "PD2_54") (pintype "bidirectional"))
    )
    (net (code "62") (name "PUP") (class "Default")
      (node (ref "R1") (pin "1") (pinfunction "1_1") (pintype "passive"))
      (node (ref "U1") (pin "1") (pinfunction "A0_1") (pintype "input"))
      (node (ref "U1") (pin "2") (pinfunction "A1_2") (pintype "input"))
      (node (ref "U1") (pin "21") (pinfunction "A2_21") (pintype "input"))
    )
    (net (code "63") (name "PWM_B") (class "Default")
      (node (ref "P3X") (pin "7") (pinfunction "7_7") (pintype "passive"))
      (node (ref "U4") (pin "21") (pinfunction "PA5_21") (pintype "bidirectional"))
    )
    (net (code "64") (name "PWM_G") (class "Default")
      (node (ref "P3X") (pin "6") (pinfunction "6_6") (pintype "passive"))
      (node (ref "U4") (pin "22") (pinfunction "PA6_22") (pintype "bidirectional"))
    )
    (net (code "65") (name "PWM_R") (class "Default")
      (node (ref "P3X") (pin "5") (pinfunction "5_5") (pintype "passive"))
      (node (ref "U4") (pin "23") (pinfunction "PA7_23") (pintype "bidirectional"))
    )
    (net (code "66") (name "RI_FTDI") (class "Default")
      (node (ref "U2") (pin "6") (pinfunction "_RI_6") (pintype "input"))
    )
    (net (code "67") (name "RTS_BMD") (class "Default")
      (node (ref "P4X") (pin "11") (pinfunction "11_11") (pintype "passive"))
      (node (ref "U4") (pin "44") (pinfunction "PA11_44") (pintype "bidirectional"))
    )
    (net (code "68") (name "RTS_FTDI") (class "Default")
      (node (ref "U2") (pin "3") (pinfunction "_RTS_3") (pintype "output"))
      (node (ref "U4") (pin "14") (pinfunction "PA0_14") (pintype "bidirectional"))
    )
    (net (code "69") (name "RXD_BMD") (class "Default")
      (node (ref "P4X") (pin "8") (pinfunction "8_8") (pintype "passive"))
      (node (ref "U4") (pin "42") (pinfunction "PA9_42") (pintype "bidirectional"))
    )
    (net (code "70") (name "RXD_FTDI") (class "Default")
      (node (ref "U2") (pin "5") (pinfunction "RXD_5") (pintype "input"))
      (node (ref "U4") (pin "16") (pinfunction "PA2_16") (pintype "bidirectional"))
    )
    (net (code "71") (name "RXD_UART6") (class "Default")
      (node (ref "U4") (pin "38") (pinfunction "PC7_38") (pintype "bidirectional"))
      (node (ref "UART") (pin "4") (pinfunction "4_4") (pintype "bidirectional"))
    )
    (net (code "72") (name "SC0") (class "Default")
      (node (ref "MUX0X") (pin "2") (pinfunction "2_2") (pintype "passive"))
      (node (ref "U1") (pin "5") (pinfunction "SC0_5") (pintype "passive"))
    )
    (net (code "73") (name "SC1") (class "Default")
      (node (ref "MUX1X") (pin "2") (pinfunction "2_2") (pintype "passive"))
      (node (ref "U1") (pin "7") (pinfunction "SC1_7") (pintype "passive"))
    )
    (net (code "74") (name "SC2") (class "Default")
      (node (ref "MUX2X") (pin "2") (pinfunction "2_2") (pintype "passive"))
      (node (ref "U1") (pin "9") (pinfunction "SC2_9") (pintype "passive"))
    )
    (net (code "75") (name "SC3") (class "Default")
      (node (ref "MUX3X") (pin "2") (pinfunction "2_2") (pintype "passive"))
      (node (ref "U1") (pin "11") (pinfunction "SC3_11") (pintype "passive"))
    )
    (net (code "76") (name "SC4") (class "Default")
      (node (ref "P3X") (pin "2") (pinfunction "2_2") (pintype "passive"))
      (node (ref "U1") (pin "14") (pinfunction "SC4_14") (pintype "passive"))
    )
    (net (code "77") (name "SC5") (class "Default")
      (node (ref "P4X") (pin "6") (pinfunction "6_6") (pintype "passive"))
      (node (ref "U1") (pin "16") (pinfunction "SC5_16") (pintype "passive"))
    )
    (net (code "78") (name "SC6") (class "Default")
      (node (ref "U1") (pin "18") (pinfunction "SC6_18") (pintype "passive"))
    )
    (net (code "79") (name "SC7") (class "Default")
      (node (ref "U1") (pin "20") (pinfunction "SC7_20") (pintype "passive"))
    )
    (net (code "80") (name "SD0") (class "Default")
      (node (ref "MUX0X") (pin "1") (pinfunction "1_1") (pintype "passive"))
      (node (ref "U1") (pin "4") (pinfunction "SD0_4") (pintype "passive"))
    )
    (net (code "81") (name "SD1") (class "Default")
      (node (ref "MUX1X") (pin "1") (pinfunction "1_1") (pintype "passive"))
      (node (ref "U1") (pin "6") (pinfunction "SD1_6") (pintype "passive"))
    )
    (net (code "82") (name "SD2") (class "Default")
      (node (ref "MUX2X") (pin "1") (pinfunction "1_1") (pintype "passive"))
      (node (ref "U1") (pin "8") (pinfunction "SD2_8") (pintype "passive"))
    )
    (net (code "83") (name "SD3") (class "Default")
      (node (ref "MUX3X") (pin "1") (pinfunction "1_1") (pintype "passive"))
      (node (ref "U1") (pin "10") (pinfunction "SD3_10") (pintype "passive"))
    )
    (net (code "84") (name "SD4") (class "Default")
      (node (ref "P3X") (pin "1") (pinfunction "1_1") (pintype "passive"))
      (node (ref "U1") (pin "13") (pinfunction "SD4_13") (pintype "passive"))
    )
    (net (code "85") (name "SD5") (class "Default")
      (node (ref "P4X") (pin "12") (pinfunction "12_12") (pintype "passive"))
      (node (ref "U1") (pin "15") (pinfunction "SD5_15") (pintype "passive"))
    )
    (net (code "86") (name "SD6") (class "Default")
      (node (ref "U1") (pin "17") (pinfunction "SD6_17") (pintype "passive"))
    )
    (net (code "87") (name "SD7") (class "Default")
      (node (ref "U1") (pin "19") (pinfunction "SD7_19") (pintype "passive"))
    )
    (net (code "88") (name "SWCLK_ST") (class "Default")
      (node (ref "J_ST") (pin "4") (pinfunction "ICSP_DAT/PGD_4") (pintype "bidirectional"))
      (node (ref "U4") (pin "49") (pinfunction "PA14_49") (pintype "bidirectional"))
    )
    (net (code "89") (name "SWDIO_ST") (class "Default")
      (node (ref "J_ST") (pin "2") (pinfunction "VDD_2") (pintype "power_in"))
      (node (ref "U4") (pin "46") (pinfunction "PA13_46") (pintype "bidirectional"))
    )
    (net (code "90") (name "TXD_BMD") (class "Default")
      (node (ref "P4X") (pin "9") (pinfunction "9_9") (pintype "passive"))
      (node (ref "U4") (pin "43") (pinfunction "PA10_43") (pintype "bidirectional"))
    )
    (net (code "91") (name "TXD_FTDI") (class "Default")
      (node (ref "U2") (pin "1") (pinfunction "TXD_1") (pintype "output"))
      (node (ref "U4") (pin "17") (pinfunction "PA3_17") (pintype "bidirectional"))
    )
    (net (code "92") (name "TXD_UART6") (class "Default")
      (node (ref "U4") (pin "37") (pinfunction "PC6_37") (pintype "bidirectional"))
      (node (ref "UART") (pin "5") (pinfunction "5_5") (pintype "bidirectional"))
    )
    (net (code "93") (name "USB_DM") (class "Default")
      (node (ref "C1") (pin "1") (pinfunction "1_1") (pintype "passive"))
      (node (ref "P4X") (pin "7") (pinfunction "7_7") (pintype "passive"))
      (node (ref "U2") (pin "16") (pinfunction "USBDM_16") (pintype "bidirectional"))
      (node (ref "USB1X") (pin "2") (pinfunction "D-_2") (pintype "bidirectional"))
    )
    (net (code "94") (name "USB_DP") (class "Default")
      (node (ref "C2") (pin "1") (pinfunction "1_1") (pintype "passive"))
      (node (ref "P4X") (pin "1") (pinfunction "1_1") (pintype "passive"))
      (node (ref "U2") (pin "15") (pinfunction "USBDP_15") (pintype "bidirectional"))
      (node (ref "USB1X") (pin "3") (pinfunction "D+_3") (pintype "bidirectional"))
    )
    (net (code "95") (name "VCAP") (class "Default")
      (node (ref "C20") (pin "1") (pinfunction "1_1") (pintype "passive"))
      (node (ref "U4") (pin "30") (pinfunction "VCAP1_30") (pintype "power_in"))
    )
    (net (code "96") (name "VDD") (class "Default")
      (node (ref "C10") (pin "1") (pinfunction "1_1") (pintype "passive"))
      (node (ref "C16") (pin "1") (pinfunction "1_1") (pintype "passive"))
      (node (ref "C17") (pin "1") (pinfunction "1_1") (pintype "passive"))
      (node (ref "C18") (pin "1") (pinfunction "1_1") (pintype "passive"))
      (node (ref "C19") (pin "1") (pinfunction "1_1") (pintype "passive"))
      (node (ref "C22") (pin "1") (pinfunction "1_1") (pintype "passive"))
      (node (ref "C23") (pin "1") (pinfunction "1_1") (pintype "passive"))
      (node (ref "C24") (pin "1") (pinfunction "1_1") (pintype "passive"))
      (node (ref "C25") (pin "1") (pinfunction "1_1") (pintype "passive"))
      (node (ref "C26") (pin "1") (pinfunction "1_1") (pintype "passive"))
      (node (ref "C28") (pin "1") (pinfunction "1_1") (pintype "passive"))
      (node (ref "C5") (pin "1") (pinfunction "1_1") (pintype "passive"))
      (node (ref "J_ST") (pin "1") (pinfunction "VPP/MCLR_1") (pintype "passive"))
      (node (ref "L1") (pin "2") (pinfunction "2_2") (pintype "passive"))
      (node (ref "R1") (pin "2") (pinfunction "2_2") (pintype "passive"))
      (node (ref "R10") (pin "2") (pinfunction "2_2") (pintype "passive"))
      (node (ref "R2") (pin "1") (pinfunction "1_1") (pintype "passive"))
      (node (ref "R3") (pin "1") (pinfunction "1_1") (pintype "passive"))
      (node (ref "R4") (pin "2") (pinfunction "2_2") (pintype "passive"))
      (node (ref "R6") (pin "1") (pinfunction "1_1") (pintype "passive"))
      (node (ref "R7") (pin "2") (pinfunction "2_2") (pintype "passive"))
      (node (ref "R9") (pin "1") (pinfunction "1_1") (pintype "passive"))
      (node (ref "U1") (pin "24") (pinfunction "VCC_24") (pintype "power_in"))
      (node (ref "U2") (pin "4") (pinfunction "VCCIO_4") (pintype "power_in"))
      (node (ref "U4") (pin "1") (pinfunction "VBAT_1") (pintype "power_in"))
      (node (ref "U4") (pin "19") (pinfunction "VDD_19") (pintype "power_in"))
      (node (ref "U4") (pin "32") (pinfunction "VDD_32") (pintype "power_in"))
      (node (ref "U4") (pin "48") (pinfunction "VDD_48") (pintype "power_in"))
      (node (ref "U4") (pin "64") (pinfunction "VDD_64") (pintype "power_in"))
      (node (ref "U5") (pin "5") (pinfunction "OUT_5") (pintype "passive"))
    )
    (net (code "97") (name "VDDA") (class "Default")
      (node (ref "C27") (pin "1") (pinfunction "1_1") (pintype "passive"))
      (node (ref "L1") (pin "1") (pinfunction "1_1") (pintype "passive"))
      (node (ref "U4") (pin "13") (pinfunction "VDDA/VREF+_13") (pintype "power_in"))
    )
    (net (code "98") (name "VIN_DC") (class "Default")
      (node (ref "C21") (pin "1") (pinfunction "1_1") (pintype "passive"))
      (node (ref "C9") (pin "1") (pinfunction "1_1") (pintype "passive"))
      (node (ref "P4X") (pin "2") (pinfunction "2_2") (pintype "passive"))
      (node (ref "PWR") (pin "PWR") (pinfunction "PWR_PWR") (pintype "bidirectional"))
      (node (ref "U3") (pin "3") (pinfunction "IN_3") (pintype "bidirectional"))
      (node (ref "U5") (pin "1") (pinfunction "IN_1") (pintype "input"))
      (node (ref "U5") (pin "3") (pinfunction "EN_3") (pintype "input"))
    )
    (net (code "99") (name "VXX") (class "Default")
      (node (ref "UART") (pin "3") (pinfunction "3_3") (pintype "bidirectional"))
    )
    (net (code "100") (name "unconnected-(J_ST-LVP-Pad6)") (class "Default")
      (node (ref "J_ST") (pin "6") (pinfunction "LVP_6") (pintype "bidirectional"))
    )
  )
)
